# freiBot_pro_micro_DIP_v1_0.net
KiCad netlist of a schematic drawn in EAGLE
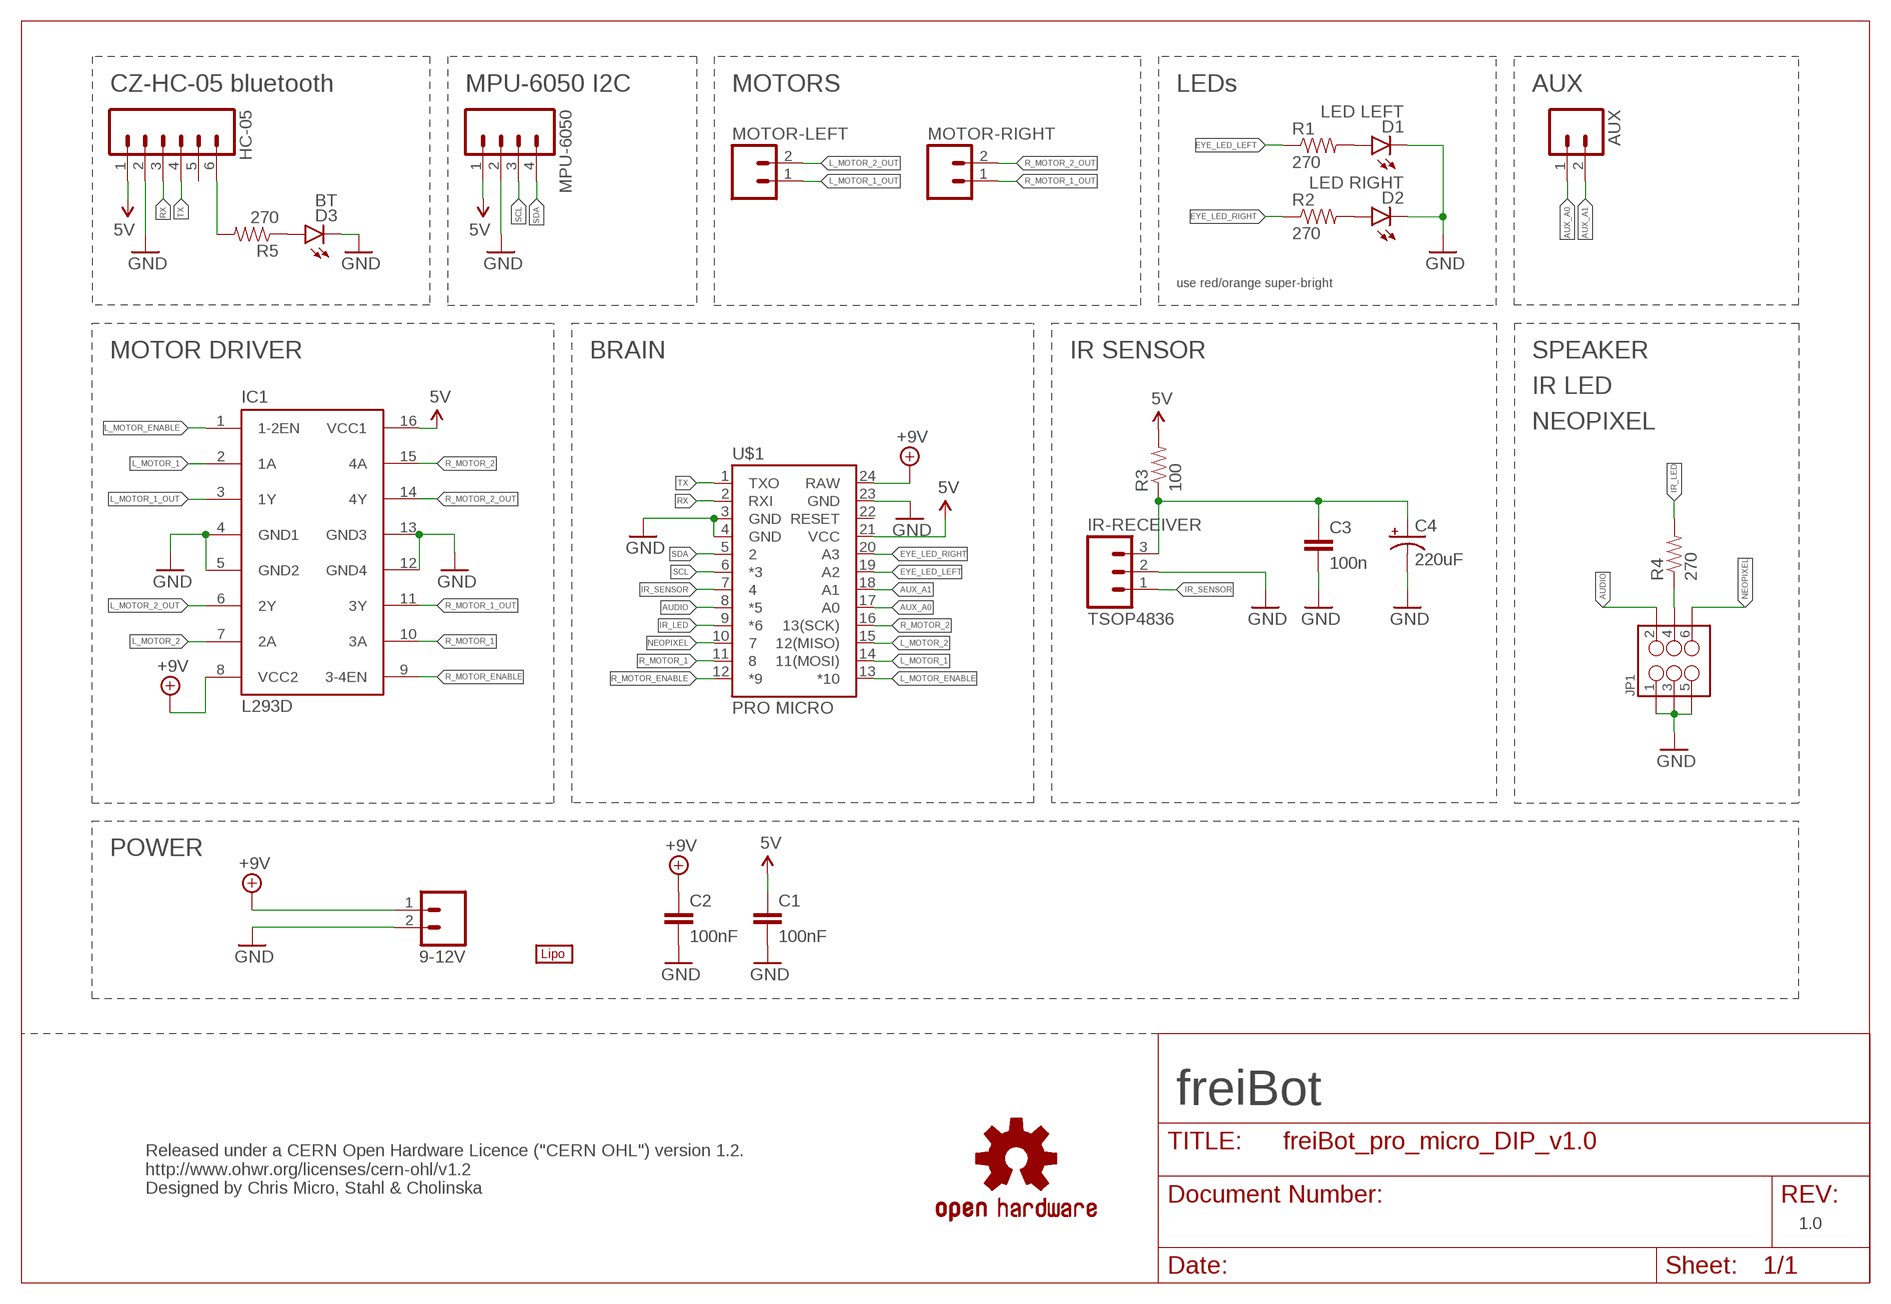
[diagram p0: schematic, sheet 1]

(export (version "E")
  (design (tool "Eeschema 10.0.6"))
  (components
    (comp (ref "9-12V")
      (value "M025MM")
      (footprint "eagle-import:SCREWTERMINAL-5MM-2")
      (libsource (lib "eagle-import") (part "M025MM"))
    )
    (comp (ref "AUX")
      (value "M02LOCK_LONGPADS")
      (footprint "eagle-import:1X02_LOCK_LONGPADS")
      (libsource (lib "eagle-import") (part "M02LOCK_LONGPADS"))
    )
    (comp (ref "C1")
      (value "100nF")
      (footprint "eagle-import:CAP-PTH-SMALL-KIT")
      (libsource (lib "eagle-import") (part "0.1UF-50V-20%(PTH)KIT-EZ"))
    )
    (comp (ref "C2")
      (value "100nF")
      (footprint "eagle-import:CAP-PTH-SMALL-KIT")
      (libsource (lib "eagle-import") (part "0.1UF-50V-20%(PTH)KIT-EZ"))
    )
    (comp (ref "C3")
      (value "100n")
      (footprint "eagle-import:CAP-PTH-SMALL-KIT")
      (libsource (lib "eagle-import") (part "0.1UF-50V-20%(PTH)KIT-EZ"))
    )
    (comp (ref "C4")
      (value "220uF")
      (footprint "eagle-import:CPOL-RADIAL-100UF-25V")
      (libsource (lib "eagle-import") (part "CAP_POLPTH1"))
    )
    (comp (ref "D1")
      (value "LED LEFT")
      (footprint "eagle-import:LED3MM")
      (libsource (lib "eagle-import") (part "LED3MM"))
    )
    (comp (ref "D2")
      (value "LED RIGHT")
      (footprint "eagle-import:LED3MM")
      (libsource (lib "eagle-import") (part "LED3MM"))
    )
    (comp (ref "D3")
      (value "BT")
      (footprint "eagle-import:LED3MM")
      (libsource (lib "eagle-import") (part "LED3MM"))
    )
    (comp (ref "HC-05")
      (value "M06LONGPADS")
      (footprint "eagle-import:1X06_LONGPADS")
      (libsource (lib "eagle-import") (part "M06LONGPADS"))
    )
    (comp (ref "IC1")
      (value "L293D")
      (footprint "eagle-import:DIL16")
      (libsource (lib "eagle-import") (part "L293D"))
    )
    (comp (ref "IR-RECEIVER")
      (value "TSOP4836")
      (footprint "eagle-import:1X03_LONGPADS")
      (libsource (lib "eagle-import") (part "M03LONGPADS"))
    )
    (comp (ref "JP1")
      (value "M03X2NO_SILK")
      (footprint "eagle-import:2X3-NS")
      (libsource (lib "eagle-import") (part "M03X2NO_SILK"))
    )
    (comp (ref "LOGO1")
      (value "OSHW-LOGOL-COPPER")
      (footprint "eagle-import:OSHW-LOGO-L_COPPER")
      (libsource (lib "eagle-import") (part "OSHW-LOGOL-COPPER"))
    )
    (comp (ref "MOTOR-LEFT")
      (value "M025MM")
      (footprint "eagle-import:SCREWTERMINAL-5MM-2")
      (libsource (lib "eagle-import") (part "M025MM"))
    )
    (comp (ref "MOTOR-RIGHT")
      (value "M025MM")
      (footprint "eagle-import:SCREWTERMINAL-5MM-2")
      (libsource (lib "eagle-import") (part "M025MM"))
    )
    (comp (ref "MPU-6050")
      (value "M04LONGPADS")
      (footprint "eagle-import:1X04_LONGPADS")
      (libsource (lib "eagle-import") (part "M04LONGPADS"))
    )
    (comp (ref "R1")
      (value "270")
      (footprint "eagle-import:AXIAL-0.3-KIT")
      (libsource (lib "eagle-import") (part "RESISTORKIT"))
    )
    (comp (ref "R2")
      (value "270")
      (footprint "eagle-import:AXIAL-0.3-KIT")
      (libsource (lib "eagle-import") (part "RESISTORKIT"))
    )
    (comp (ref "R3")
      (value "100")
      (footprint "eagle-import:AXIAL-0.3-KIT")
      (libsource (lib "eagle-import") (part "RESISTORKIT"))
    )
    (comp (ref "R4")
      (value "270")
      (footprint "eagle-import:AXIAL-0.3-KIT")
      (libsource (lib "eagle-import") (part "RESISTORKIT"))
    )
    (comp (ref "R5")
      (value "270")
      (footprint "eagle-import:AXIAL-0.3-KIT")
      (libsource (lib "eagle-import") (part "RESISTORKIT"))
    )
    (comp (ref "U$1")
      (value "PRO MICRO")
      (footprint "eagle-import:ARDUINO_PRO_MICRO")
      (libsource (lib "eagle-import") (part "ARDUINO_PRO_MICRO"))
    )
    (comp (ref "U$2")
      (value "LIPO-OUTLINE2000")
      (footprint "eagle-import:LIPO-2000")
      (libsource (lib "eagle-import") (part "LIPO-OUTLINE2000"))
    )
  )
  (nets
    (net (code "1") (name "+9V") (class "Default")
      (node (ref "9-12V") (pin "1") (pinfunction "1_1") (pintype "passive"))
      (node (ref "C2") (pin "1") (pinfunction "1_1") (pintype "passive"))
      (node (ref "IC1") (pin "8") (pinfunction "VCC2_8") (pintype "power_in"))
      (node (ref "U$1") (pin "24") (pinfunction "RAW_24") (pintype "bidirectional"))
    )
    (net (code "2") (name "5V") (class "Default")
      (node (ref "C1") (pin "1") (pinfunction "1_1") (pintype "passive"))
      (node (ref "HC-05") (pin "1") (pinfunction "1_1") (pintype "passive"))
      (node (ref "IC1") (pin "16") (pinfunction "VCC1_16") (pintype "power_in"))
      (node (ref "MPU-6050") (pin "1") (pinfunction "1_1") (pintype "passive"))
      (node (ref "R3") (pin "P$2") (pinfunction "2_P$2") (pintype "passive"))
      (node (ref "U$1") (pin "21") (pinfunction "VCC_21") (pintype "bidirectional"))
    )
    (net (code "3") (name "AUDIO") (class "Default")
      (node (ref "JP1") (pin "2") (pinfunction "2_2") (pintype "bidirectional"))
      (node (ref "U$1") (pin "8") (pinfunction "*5_8") (pintype "bidirectional"))
    )
    (net (code "4") (name "AUX_A0") (class "Default")
      (node (ref "AUX") (pin "1") (pinfunction "1_1") (pintype "passive"))
      (node (ref "U$1") (pin "17") (pinfunction "A0_17") (pintype "bidirectional"))
    )
    (net (code "5") (name "AUX_A1") (class "Default")
      (node (ref "AUX") (pin "2") (pinfunction "2_2") (pintype "passive"))
      (node (ref "U$1") (pin "18") (pinfunction "A1_18") (pintype "bidirectional"))
    )
    (net (code "6") (name "EYE_LED_LEFT") (class "Default")
      (node (ref "R1") (pin "P$1") (pinfunction "1_P$1") (pintype "passive"))
      (node (ref "U$1") (pin "19") (pinfunction "A2_19") (pintype "bidirectional"))
    )
    (net (code "7") (name "EYE_LED_RIGHT") (class "Default")
      (node (ref "R2") (pin "P$1") (pinfunction "1_P$1") (pintype "passive"))
      (node (ref "U$1") (pin "20") (pinfunction "A3_20") (pintype "bidirectional"))
    )
    (net (code "8") (name "GND") (class "Default")
      (node (ref "9-12V") (pin "2") (pinfunction "2_2") (pintype "passive"))
      (node (ref "C1") (pin "2") (pinfunction "2_2") (pintype "passive"))
      (node (ref "C2") (pin "2") (pinfunction "2_2") (pintype "passive"))
      (node (ref "C3") (pin "2") (pinfunction "2_2") (pintype "passive"))
      (node (ref "C4") (pin "2") (pinfunction "-_2") (pintype "passive"))
      (node (ref "D1") (pin "K") (pinfunction "C_K") (pintype "passive"))
      (node (ref "D2") (pin "K") (pinfunction "C_K") (pintype "passive"))
      (node (ref "D3") (pin "K") (pinfunction "C_K") (pintype "passive"))
      (node (ref "HC-05") (pin "2") (pinfunction "2_2") (pintype "passive"))
      (node (ref "IC1") (pin "12") (pinfunction "GND4_12") (pintype "power_in"))
      (node (ref "IC1") (pin "13") (pinfunction "GND3_13") (pintype "power_in"))
      (node (ref "IC1") (pin "4") (pinfunction "GND1_4") (pintype "power_in"))
      (node (ref "IC1") (pin "5") (pinfunction "GND2_5") (pintype "power_in"))
      (node (ref "IR-RECEIVER") (pin "2") (pinfunction "2_2") (pintype "passive"))
      (node (ref "JP1") (pin "1") (pinfunction "1_1") (pintype "bidirectional"))
      (node (ref "JP1") (pin "3") (pinfunction "3_3") (pintype "bidirectional"))
      (node (ref "JP1") (pin "5") (pinfunction "5_5") (pintype "bidirectional"))
      (node (ref "MPU-6050") (pin "2") (pinfunction "2_2") (pintype "passive"))
      (node (ref "U$1") (pin "23") (pinfunction "GND_23") (pintype "bidirectional"))
      (node (ref "U$1") (pin "3") (pinfunction "GND_3") (pintype "bidirectional"))
      (node (ref "U$1") (pin "4") (pinfunction "GND_4") (pintype "bidirectional"))
    )
    (net (code "9") (name "IR_LED") (class "Default")
      (node (ref "R4") (pin "P$2") (pinfunction "2_P$2") (pintype "passive"))
      (node (ref "U$1") (pin "9") (pinfunction "*6_9") (pintype "bidirectional"))
    )
    (net (code "10") (name "IR_SENSOR") (class "Default")
      (node (ref "IR-RECEIVER") (pin "1") (pinfunction "1_1") (pintype "passive"))
      (node (ref "U$1") (pin "7") (pinfunction "4_7") (pintype "bidirectional"))
    )
    (net (code "11") (name "L_MOTOR_1") (class "Default")
      (node (ref "IC1") (pin "2") (pinfunction "1A_2") (pintype "input"))
      (node (ref "U$1") (pin "14") (pinfunction "11(MOSI)_14") (pintype "bidirectional"))
    )
    (net (code "12") (name "L_MOTOR_1_OUT") (class "Default")
      (node (ref "IC1") (pin "3") (pinfunction "1Y_3") (pintype "output"))
      (node (ref "MOTOR-LEFT") (pin "1") (pinfunction "1_1") (pintype "passive"))
    )
    (net (code "13") (name "L_MOTOR_2") (class "Default")
      (node (ref "IC1") (pin "7") (pinfunction "2A_7") (pintype "input"))
      (node (ref "U$1") (pin "15") (pinfunction "12(MISO)_15") (pintype "bidirectional"))
    )
    (net (code "14") (name "L_MOTOR_2_OUT") (class "Default")
      (node (ref "IC1") (pin "6") (pinfunction "2Y_6") (pintype "output"))
      (node (ref "MOTOR-LEFT") (pin "2") (pinfunction "2_2") (pintype "passive"))
    )
    (net (code "15") (name "L_MOTOR_ENABLE") (class "Default")
      (node (ref "IC1") (pin "1") (pinfunction "1-2EN_1") (pintype "input"))
      (node (ref "U$1") (pin "13") (pinfunction "*10_13") (pintype "bidirectional"))
    )
    (net (code "16") (name "NEOPIXEL") (class "Default")
      (node (ref "JP1") (pin "6") (pinfunction "6_6") (pintype "bidirectional"))
      (node (ref "U$1") (pin "10") (pinfunction "7_10") (pintype "bidirectional"))
    )
    (net (code "17") (name "Net-(C4-+)") (class "Default")
      (node (ref "C3") (pin "1") (pinfunction "1_1") (pintype "passive"))
      (node (ref "C4") (pin "1") (pinfunction "+_1") (pintype "passive"))
      (node (ref "IR-RECEIVER") (pin "3") (pinfunction "3_3") (pintype "passive"))
      (node (ref "R3") (pin "P$1") (pinfunction "1_P$1") (pintype "passive"))
    )
    (net (code "18") (name "Net-(R1-2)") (class "Default")
      (node (ref "D1") (pin "A") (pinfunction "A_A") (pintype "passive"))
      (node (ref "R1") (pin "P$2") (pinfunction "2_P$2") (pintype "passive"))
    )
    (net (code "19") (name "Net-(R2-2)") (class "Default")
      (node (ref "D2") (pin "A") (pinfunction "A_A") (pintype "passive"))
      (node (ref "R2") (pin "P$2") (pinfunction "2_P$2") (pintype "passive"))
    )
    (net (code "20") (name "Net-(R4-1)") (class "Default")
      (node (ref "JP1") (pin "4") (pinfunction "4_4") (pintype "bidirectional"))
      (node (ref "R4") (pin "P$1") (pinfunction "1_P$1") (pintype "passive"))
    )
    (net (code "21") (name "Net-(R5-1)") (class "Default")
      (node (ref "D3") (pin "A") (pinfunction "A_A") (pintype "passive"))
      (node (ref "R5") (pin "P$1") (pinfunction "1_P$1") (pintype "passive"))
    )
    (net (code "22") (name "Net-(R5-2)") (class "Default")
      (node (ref "HC-05") (pin "6") (pinfunction "6_6") (pintype "passive"))
      (node (ref "R5") (pin "P$2") (pinfunction "2_P$2") (pintype "passive"))
    )
    (net (code "23") (name "RX") (class "Default")
      (node (ref "HC-05") (pin "3") (pinfunction "3_3") (pintype "passive"))
      (node (ref "U$1") (pin "2") (pinfunction "RXI_2") (pintype "bidirectional"))
    )
    (net (code "24") (name "R_MOTOR_1") (class "Default")
      (node (ref "IC1") (pin "10") (pinfunction "3A_10") (pintype "input"))
      (node (ref "U$1") (pin "11") (pinfunction "8_11") (pintype "bidirectional"))
    )
    (net (code "25") (name "R_MOTOR_1_OUT") (class "Default")
      (node (ref "IC1") (pin "11") (pinfunction "3Y_11") (pintype "output"))
      (node (ref "MOTOR-RIGHT") (pin "1") (pinfunction "1_1") (pintype "passive"))
    )
    (net (code "26") (name "R_MOTOR_2") (class "Default")
      (node (ref "IC1") (pin "15") (pinfunction "4A_15") (pintype "input"))
      (node (ref "U$1") (pin "16") (pinfunction "13(SCK)_16") (pintype "bidirectional"))
    )
    (net (code "27") (name "R_MOTOR_2_OUT") (class "Default")
      (node (ref "IC1") (pin "14") (pinfunction "4Y_14") (pintype "output"))
      (node (ref "MOTOR-RIGHT") (pin "2") (pinfunction "2_2") (pintype "passive"))
    )
    (net (code "28") (name "R_MOTOR_ENABLE") (class "Default")
      (node (ref "IC1") (pin "9") (pinfunction "3-4EN_9") (pintype "input"))
      (node (ref "U$1") (pin "12") (pinfunction "*9_12") (pintype "bidirectional"))
    )
    (net (code "29") (name "SCL") (class "Default")
      (node (ref "MPU-6050") (pin "3") (pinfunction "3_3") (pintype "passive"))
      (node (ref "U$1") (pin "6") (pinfunction "*3_6") (pintype "bidirectional"))
    )
    (net (code "30") (name "SDA") (class "Default")
      (node (ref "MPU-6050") (pin "4") (pinfunction "4_4") (pintype "passive"))
      (node (ref "U$1") (pin "5") (pinfunction "2_5") (pintype "bidirectional"))
    )
    (net (code "31") (name "TX") (class "Default")
      (node (ref "HC-05") (pin "4") (pinfunction "4_4") (pintype "passive"))
      (node (ref "U$1") (pin "1") (pinfunction "TXO_1") (pintype "bidirectional"))
    )
    (net (code "32") (name "unconnected-(HC-05-Pad5)") (class "Default")
      (node (ref "HC-05") (pin "5") (pinfunction "5_5") (pintype "passive"))
    )
    (net (code "33") (name "unconnected-(U$1-RESET-Pad22)") (class "Default")
      (node (ref "U$1") (pin "22") (pinfunction "RESET_22") (pintype "bidirectional"))
    )
  )
)
